# SCH_MAGPIE_DS3_Nano_PDB_v1_1_2022-03-11.net
KiCad netlist of a schematic drawn in EasyEDA
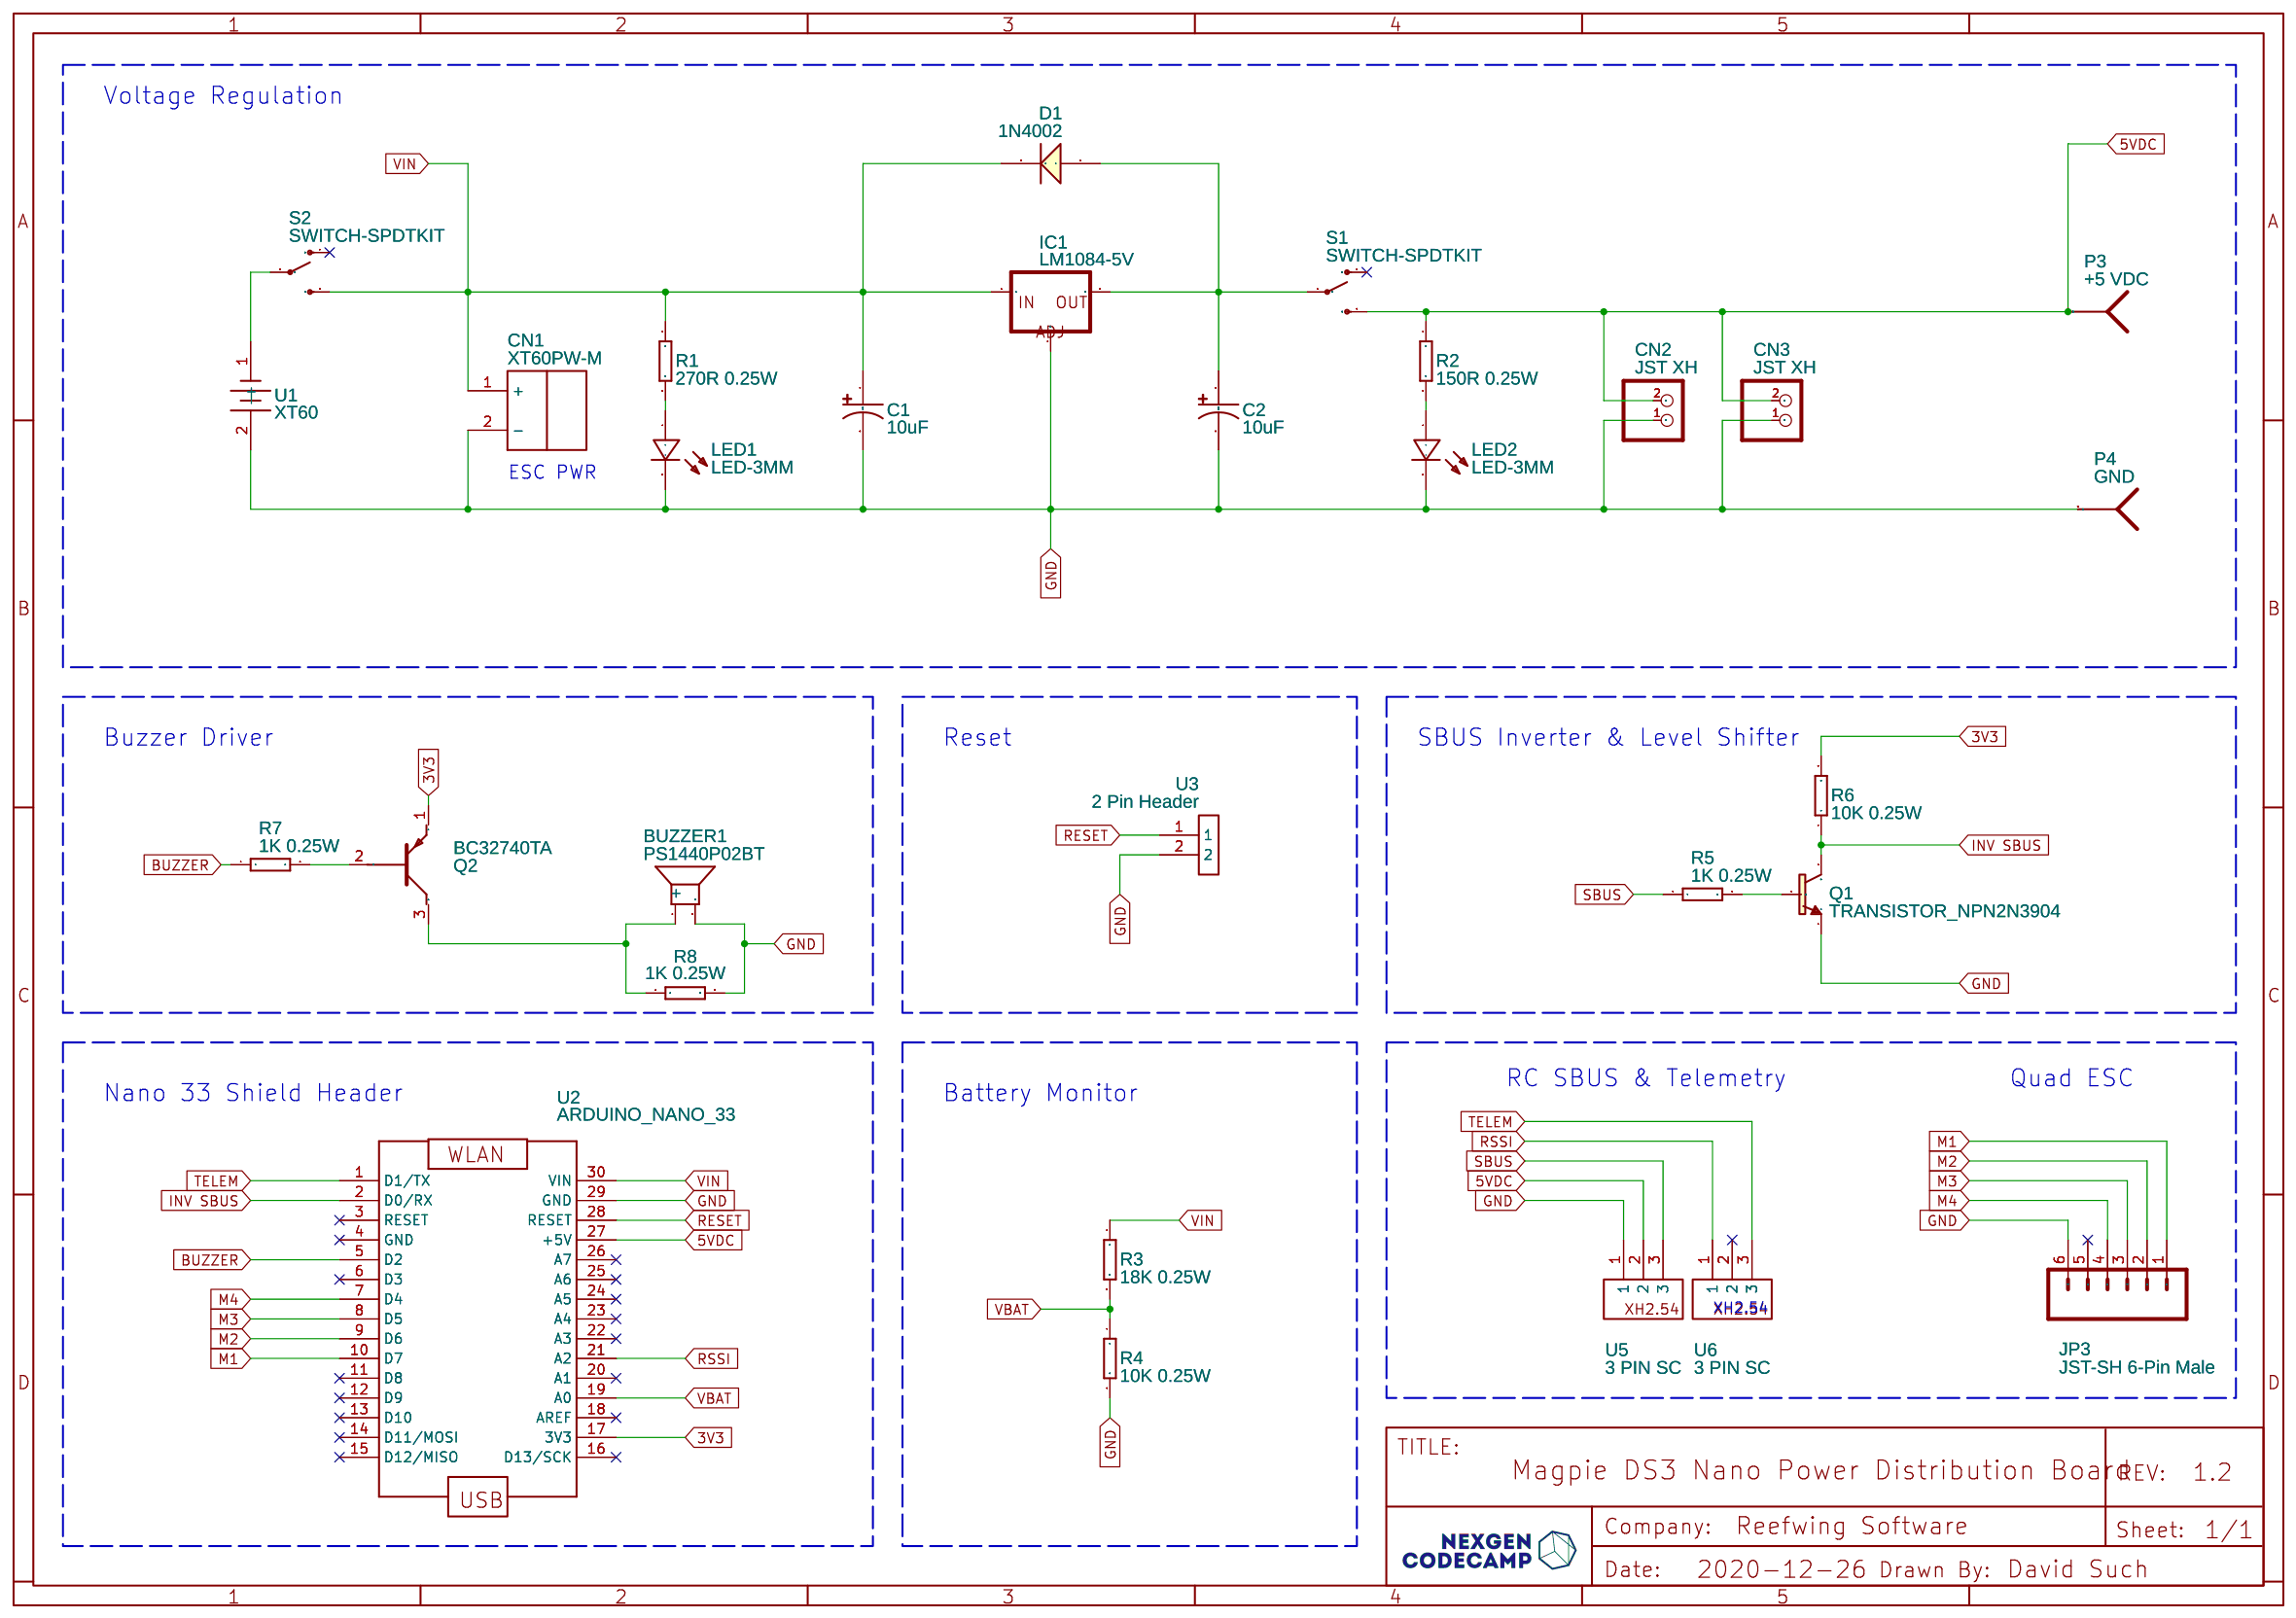
[diagram p0: schematic sheet]

(export (version "E")
  (design (tool "Eeschema 10.0.6"))
  (components
    (comp (ref "BUZZER1")
      (value "PS1440P02BT")
      (fields (field (name "BOM_Supplier Part") "C96060"))
      (libsource (lib "") (part "PS1440P02BT"))
    )
    (comp (ref "C1") (value "10uF") (libsource (lib "") (part "Cap_Tantalum(TH)_TAN-S2.5_US")))
    (comp (ref "C2") (value "10uF") (libsource (lib "") (part "Cap_Tantalum(TH)_TAN-S2.5_US")))
    (comp (ref "CN1")
      (value "XT60PW-M")
      (fields (field (name "BOM_Supplier Part") "C98732"))
      (libsource (lib "") (part "XT60PW-M"))
    )
    (comp (ref "CN2") (value "JST XH") (libsource (lib "") (part "JST_2PIN-THM")))
    (comp (ref "CN3") (value "JST XH") (libsource (lib "") (part "JST_2PIN-THM")))
    (comp (ref "D1") (value "1N4002") (libsource (lib "") (part "1N4002")))
    (comp (ref "IC1") (value "LM1084-5V") (libsource (lib "") (part "LM1084-V")))
    (comp (ref "JP3")
      (value "JST-SH 6-Pin Male")
      (libsource (lib "") (part "Micro JST 6-Pin Male PCB Connector 1.25mm"))
    )
    (comp (ref "LED1")
      (value "LED-3MM")
      (fields
        (field (name "BOM_Manufacturer Part") "204-10SURD/S530-A3")
        (field (name "BOM_Supplier Part") "C99772")
      )
      (libsource (lib "") (part "LED-3MM"))
    )
    (comp (ref "LED2")
      (value "LED-3MM")
      (fields
        (field (name "BOM_Manufacturer Part") "204-10SURD/S530-A3")
        (field (name "BOM_Supplier Part") "C99772")
      )
      (libsource (lib "") (part "LED-3MM"))
    )
    (comp (ref "P3") (value "+5 VDC") (libsource (lib "") (part "INPUT_CONNECTOR")))
    (comp (ref "P4") (value "GND") (libsource (lib "") (part "INPUT_CONNECTOR")))
    (comp (ref "Q1") (value "TRANSISTOR_NPN2N3904") (libsource (lib "") (part "TRANSISTOR_NPN2N3904")))
    (comp (ref "Q2") (value "BC32740TA") (libsource (lib "") (part "BC32740TA")))
    (comp (ref "R1") (value "270R 0.25W") (libsource (lib "") (part "RESISTOR")))
    (comp (ref "R2") (value "150R 0.25W") (libsource (lib "") (part "RESISTOR")))
    (comp (ref "R3") (value "18K 0.25W") (libsource (lib "") (part "RESISTOR")))
    (comp (ref "R4") (value "10K 0.25W") (libsource (lib "") (part "RESISTOR")))
    (comp (ref "R5") (value "1K 0.25W") (libsource (lib "") (part "RESISTOR_2")))
    (comp (ref "R6") (value "10K 0.25W") (libsource (lib "") (part "RESISTOR_1")))
    (comp (ref "R7") (value "1K 0.25W") (libsource (lib "") (part "RESISTOR_2")))
    (comp (ref "R8") (value "1K 0.25W") (libsource (lib "") (part "RESISTOR_2")))
    (comp (ref "S1") (value "SWITCH-SPDTKIT") (libsource (lib "") (part "SWITCH-SPDTKIT")))
    (comp (ref "S2") (value "SWITCH-SPDTKIT") (libsource (lib "") (part "SWITCH-SPDTKIT")))
    (comp (ref "U1")
      (value "XT60")
      (fields (field (name "BOM_Manufacturer Part") "X"))
      (libsource (lib "") (part "XT60"))
    )
    (comp (ref "U2") (value "ARDUINO_NANO_33") (libsource (lib "") (part "ARDUINO_NANO_33_IoT")))
    (comp (ref "U3")
      (value "2 Pin Header")
      (fields (field (name "BOM_Manufacturer Part") "Male Header 2 pin"))
      (libsource (lib "") (part "2 Pin Header"))
    )
    (comp (ref "U5")
      (value "3 PIN SC")
      (fields (field (name "BOM_Manufacturer Part") "New SchematicLib"))
      (libsource (lib "") (part "XH2.54_3_PIn_Connector"))
    )
    (comp (ref "U6")
      (value "3 PIN SC")
      (fields (field (name "BOM_Manufacturer Part") "New SchematicLib"))
      (libsource (lib "") (part "XH2.54_3_PIn_Connector"))
    )
  )
  (nets
    (net (code "1") (name "3V3") (class "Default")
      (node (ref "Q2") (pin "1") (pinfunction "E_1") (pintype "bidirectional"))
      (node (ref "R6") (pin "2") (pinfunction "2_2") (pintype "unspecified"))
      (node (ref "U2") (pin "17") (pinfunction "3V3_17") (pintype "unspecified"))
    )
    (net (code "2") (name "5VDC") (class "Default")
      (node (ref "CN2") (pin "2") (pinfunction "1_2") (pintype "unspecified"))
      (node (ref "CN3") (pin "2") (pinfunction "1_2") (pintype "unspecified"))
      (node (ref "P3") (pin "P$1") (pinfunction "P$1_P$1") (pintype "output"))
      (node (ref "R2") (pin "1") (pinfunction "1_1") (pintype "unspecified"))
      (node (ref "S1") (pin "3") (pinfunction "S_3") (pintype "unspecified"))
      (node (ref "U2") (pin "27") (pinfunction "+5V_27") (pintype "unspecified"))
      (node (ref "U5") (pin "2") (pinfunction "2_2") (pintype "unspecified"))
    )
    (net (code "3") (name "BUZZER") (class "Default")
      (node (ref "R7") (pin "1") (pinfunction "1_1") (pintype "unspecified"))
      (node (ref "U2") (pin "5") (pinfunction "D2_5") (pintype "unspecified"))
    )
    (net (code "4") (name "GND") (class "Default")
      (node (ref "BUZZER1") (pin "2") (pinfunction "2_2") (pintype "unspecified"))
      (node (ref "C1") (pin "2") (pinfunction "2_2") (pintype "unspecified"))
      (node (ref "C2") (pin "2") (pinfunction "2_2") (pintype "unspecified"))
      (node (ref "CN1") (pin "2") (pinfunction "-_2") (pintype "unspecified"))
      (node (ref "CN2") (pin "1") (pinfunction "2_1") (pintype "unspecified"))
      (node (ref "CN3") (pin "1") (pinfunction "2_1") (pintype "unspecified"))
      (node (ref "IC1") (pin "1") (pinfunction "ADJ_1") (pintype "input"))
      (node (ref "JP3") (pin "6") (pinfunction "6_6") (pintype "unspecified"))
      (node (ref "LED1") (pin "2") (pinfunction "-_2") (pintype "unspecified"))
      (node (ref "LED2") (pin "2") (pinfunction "-_2") (pintype "unspecified"))
      (node (ref "P4") (pin "P$1") (pinfunction "P$1_P$1") (pintype "output"))
      (node (ref "Q1") (pin "1") (pinfunction "E_1") (pintype "unspecified"))
      (node (ref "R4") (pin "2") (pinfunction "2_2") (pintype "unspecified"))
      (node (ref "R8") (pin "2") (pinfunction "2_2") (pintype "unspecified"))
      (node (ref "U1") (pin "2") (pinfunction "-_2") (pintype "unspecified"))
      (node (ref "U2") (pin "29") (pinfunction "GND_29") (pintype "unspecified"))
      (node (ref "U3") (pin "2") (pinfunction "2_2") (pintype "unspecified"))
      (node (ref "U5") (pin "1") (pinfunction "1_1") (pintype "unspecified"))
    )
    (net (code "5") (name "INV SBUS") (class "Default")
      (node (ref "Q1") (pin "3") (pinfunction "C_3") (pintype "unspecified"))
      (node (ref "R6") (pin "1") (pinfunction "1_1") (pintype "unspecified"))
      (node (ref "U2") (pin "2") (pinfunction "D0/RX_2") (pintype "unspecified"))
    )
    (net (code "6") (name "M1") (class "Default")
      (node (ref "JP3") (pin "1") (pinfunction "1_1") (pintype "unspecified"))
      (node (ref "U2") (pin "10") (pinfunction "D7_10") (pintype "unspecified"))
    )
    (net (code "7") (name "M2") (class "Default")
      (node (ref "JP3") (pin "2") (pinfunction "2_2") (pintype "unspecified"))
      (node (ref "U2") (pin "9") (pinfunction "D6_9") (pintype "unspecified"))
    )
    (net (code "8") (name "M3") (class "Default")
      (node (ref "JP3") (pin "3") (pinfunction "3_3") (pintype "unspecified"))
      (node (ref "U2") (pin "8") (pinfunction "D5_8") (pintype "unspecified"))
    )
    (net (code "9") (name "M4") (class "Default")
      (node (ref "JP3") (pin "4") (pinfunction "4_4") (pintype "unspecified"))
      (node (ref "U2") (pin "7") (pinfunction "D4_7") (pintype "unspecified"))
    )
    (net (code "10") (name "Net-(BUZZER1-+)") (class "Default")
      (node (ref "BUZZER1") (pin "1") (pinfunction "+_1") (pintype "unspecified"))
      (node (ref "Q2") (pin "3") (pinfunction "C_3") (pintype "bidirectional"))
      (node (ref "R8") (pin "1") (pinfunction "1_1") (pintype "unspecified"))
    )
    (net (code "11") (name "Net-(D1-A)") (class "Default")
      (node (ref "C2") (pin "1") (pinfunction "1_1") (pintype "unspecified"))
      (node (ref "D1") (pin "1") (pinfunction "A_1") (pintype "unspecified"))
      (node (ref "IC1") (pin "2") (pinfunction "OUT_2") (pintype "unspecified"))
      (node (ref "S1") (pin "2") (pinfunction "P_2") (pintype "unspecified"))
    )
    (net (code "12") (name "Net-(LED1-+)") (class "Default")
      (node (ref "LED1") (pin "1") (pinfunction "+_1") (pintype "unspecified"))
      (node (ref "R1") (pin "2") (pinfunction "2_2") (pintype "unspecified"))
    )
    (net (code "13") (name "Net-(LED2-+)") (class "Default")
      (node (ref "LED2") (pin "1") (pinfunction "+_1") (pintype "unspecified"))
      (node (ref "R2") (pin "2") (pinfunction "2_2") (pintype "unspecified"))
    )
    (net (code "14") (name "Net-(Q1-B)") (class "Default")
      (node (ref "Q1") (pin "2") (pinfunction "B_2") (pintype "unspecified"))
      (node (ref "R5") (pin "2") (pinfunction "2_2") (pintype "unspecified"))
    )
    (net (code "15") (name "Net-(Q2-B)") (class "Default")
      (node (ref "Q2") (pin "2") (pinfunction "B_2") (pintype "bidirectional"))
      (node (ref "R7") (pin "2") (pinfunction "2_2") (pintype "unspecified"))
    )
    (net (code "16") (name "Net-(S2-P)") (class "Default")
      (node (ref "S2") (pin "2") (pinfunction "P_2") (pintype "unspecified"))
      (node (ref "U1") (pin "1") (pinfunction "+_1") (pintype "unspecified"))
    )
    (net (code "17") (name "RESET") (class "Default")
      (node (ref "U2") (pin "28") (pinfunction "RESET_28") (pintype "unspecified"))
      (node (ref "U3") (pin "1") (pinfunction "1_1") (pintype "unspecified"))
    )
    (net (code "18") (name "RSSI") (class "Default")
      (node (ref "U2") (pin "21") (pinfunction "A2_21") (pintype "unspecified"))
      (node (ref "U6") (pin "1") (pinfunction "1_1") (pintype "unspecified"))
    )
    (net (code "19") (name "SBUS") (class "Default")
      (node (ref "R5") (pin "1") (pinfunction "1_1") (pintype "unspecified"))
      (node (ref "U5") (pin "3") (pinfunction "3_3") (pintype "unspecified"))
    )
    (net (code "20") (name "TELEM") (class "Default")
      (node (ref "U2") (pin "1") (pinfunction "D1/TX_1") (pintype "unspecified"))
      (node (ref "U6") (pin "3") (pinfunction "3_3") (pintype "unspecified"))
    )
    (net (code "21") (name "VBAT") (class "Default")
      (node (ref "R3") (pin "2") (pinfunction "2_2") (pintype "unspecified"))
      (node (ref "R4") (pin "1") (pinfunction "1_1") (pintype "unspecified"))
      (node (ref "U2") (pin "19") (pinfunction "A0_19") (pintype "unspecified"))
    )
    (net (code "22") (name "VIN") (class "Default")
      (node (ref "C1") (pin "1") (pinfunction "1_1") (pintype "unspecified"))
      (node (ref "CN1") (pin "1") (pinfunction "+_1") (pintype "unspecified"))
      (node (ref "D1") (pin "2") (pinfunction "K_2") (pintype "unspecified"))
      (node (ref "IC1") (pin "3") (pinfunction "IN_3") (pintype "input"))
      (node (ref "R1") (pin "1") (pinfunction "1_1") (pintype "unspecified"))
      (node (ref "R3") (pin "1") (pinfunction "1_1") (pintype "unspecified"))
      (node (ref "S2") (pin "3") (pinfunction "S_3") (pintype "unspecified"))
      (node (ref "U2") (pin "30") (pinfunction "VIN_30") (pintype "unspecified"))
    )
    (net (code "23") (name "unconnected-(JP3-Pad5)") (class "Default")
      (node (ref "JP3") (pin "5") (pinfunction "5_5") (pintype "unspecified+no_connect"))
    )
    (net (code "24") (name "unconnected-(S1-O-Pad1)") (class "Default")
      (node (ref "S1") (pin "1") (pinfunction "O_1") (pintype "unspecified+no_connect"))
    )
    (net (code "25") (name "unconnected-(S2-O-Pad1)") (class "Default")
      (node (ref "S2") (pin "1") (pinfunction "O_1") (pintype "unspecified+no_connect"))
    )
    (net (code "26") (name "unconnected-(U2-A1-Pad20)") (class "Default")
      (node (ref "U2") (pin "20") (pinfunction "A1_20") (pintype "unspecified+no_connect"))
    )
    (net (code "27") (name "unconnected-(U2-A3-Pad22)") (class "Default")
      (node (ref "U2") (pin "22") (pinfunction "A3_22") (pintype "unspecified+no_connect"))
    )
    (net (code "28") (name "unconnected-(U2-A4-Pad23)") (class "Default")
      (node (ref "U2") (pin "23") (pinfunction "A4_23") (pintype "unspecified+no_connect"))
    )
    (net (code "29") (name "unconnected-(U2-A5-Pad24)") (class "Default")
      (node (ref "U2") (pin "24") (pinfunction "A5_24") (pintype "unspecified+no_connect"))
    )
    (net (code "30") (name "unconnected-(U2-A6-Pad25)") (class "Default")
      (node (ref "U2") (pin "25") (pinfunction "A6_25") (pintype "unspecified+no_connect"))
    )
    (net (code "31") (name "unconnected-(U2-A7-Pad26)") (class "Default")
      (node (ref "U2") (pin "26") (pinfunction "A7_26") (pintype "unspecified+no_connect"))
    )
    (net (code "32") (name "unconnected-(U2-AREF-Pad18)") (class "Default")
      (node (ref "U2") (pin "18") (pinfunction "AREF_18") (pintype "unspecified+no_connect"))
    )
    (net (code "33") (name "unconnected-(U2-D3-Pad6)") (class "Default")
      (node (ref "U2") (pin "6") (pinfunction "D3_6") (pintype "unspecified+no_connect"))
    )
    (net (code "34") (name "unconnected-(U2-D8-Pad11)") (class "Default")
      (node (ref "U2") (pin "11") (pinfunction "D8_11") (pintype "unspecified+no_connect"))
    )
    (net (code "35") (name "unconnected-(U2-D9-Pad12)") (class "Default")
      (node (ref "U2") (pin "12") (pinfunction "D9_12") (pintype "unspecified+no_connect"))
    )
    (net (code "36") (name "unconnected-(U2-D10-Pad13)") (class "Default")
      (node (ref "U2") (pin "13") (pinfunction "D10_13") (pintype "unspecified+no_connect"))
    )
    (net (code "37") (name "unconnected-(U2-D11{slash}MOSI-Pad14)") (class "Default")
      (node (ref "U2") (pin "14") (pinfunction "D11/MOSI_14") (pintype "unspecified+no_connect"))
    )
    (net (code "38") (name "unconnected-(U2-D12{slash}MISO-Pad15)") (class "Default")
      (node (ref "U2") (pin "15") (pinfunction "D12/MISO_15") (pintype "unspecified+no_connect"))
    )
    (net (code "39") (name "unconnected-(U2-D13{slash}SCK-Pad16)") (class "Default")
      (node (ref "U2") (pin "16") (pinfunction "D13/SCK_16") (pintype "unspecified+no_connect"))
    )
    (net (code "40") (name "unconnected-(U2-GND-Pad4)") (class "Default")
      (node (ref "U2") (pin "4") (pinfunction "GND_4") (pintype "unspecified+no_connect"))
    )
    (net (code "41") (name "unconnected-(U2-RESET-Pad3)") (class "Default")
      (node (ref "U2") (pin "3") (pinfunction "RESET_3") (pintype "unspecified+no_connect"))
    )
    (net (code "42") (name "unconnected-(U6-Pad2)") (class "Default")
      (node (ref "U6") (pin "2") (pinfunction "2_2") (pintype "unspecified+no_connect"))
    )
  )
)
